# PERIPH.net
KiCad netlist of a schematic drawn in Altium Designer
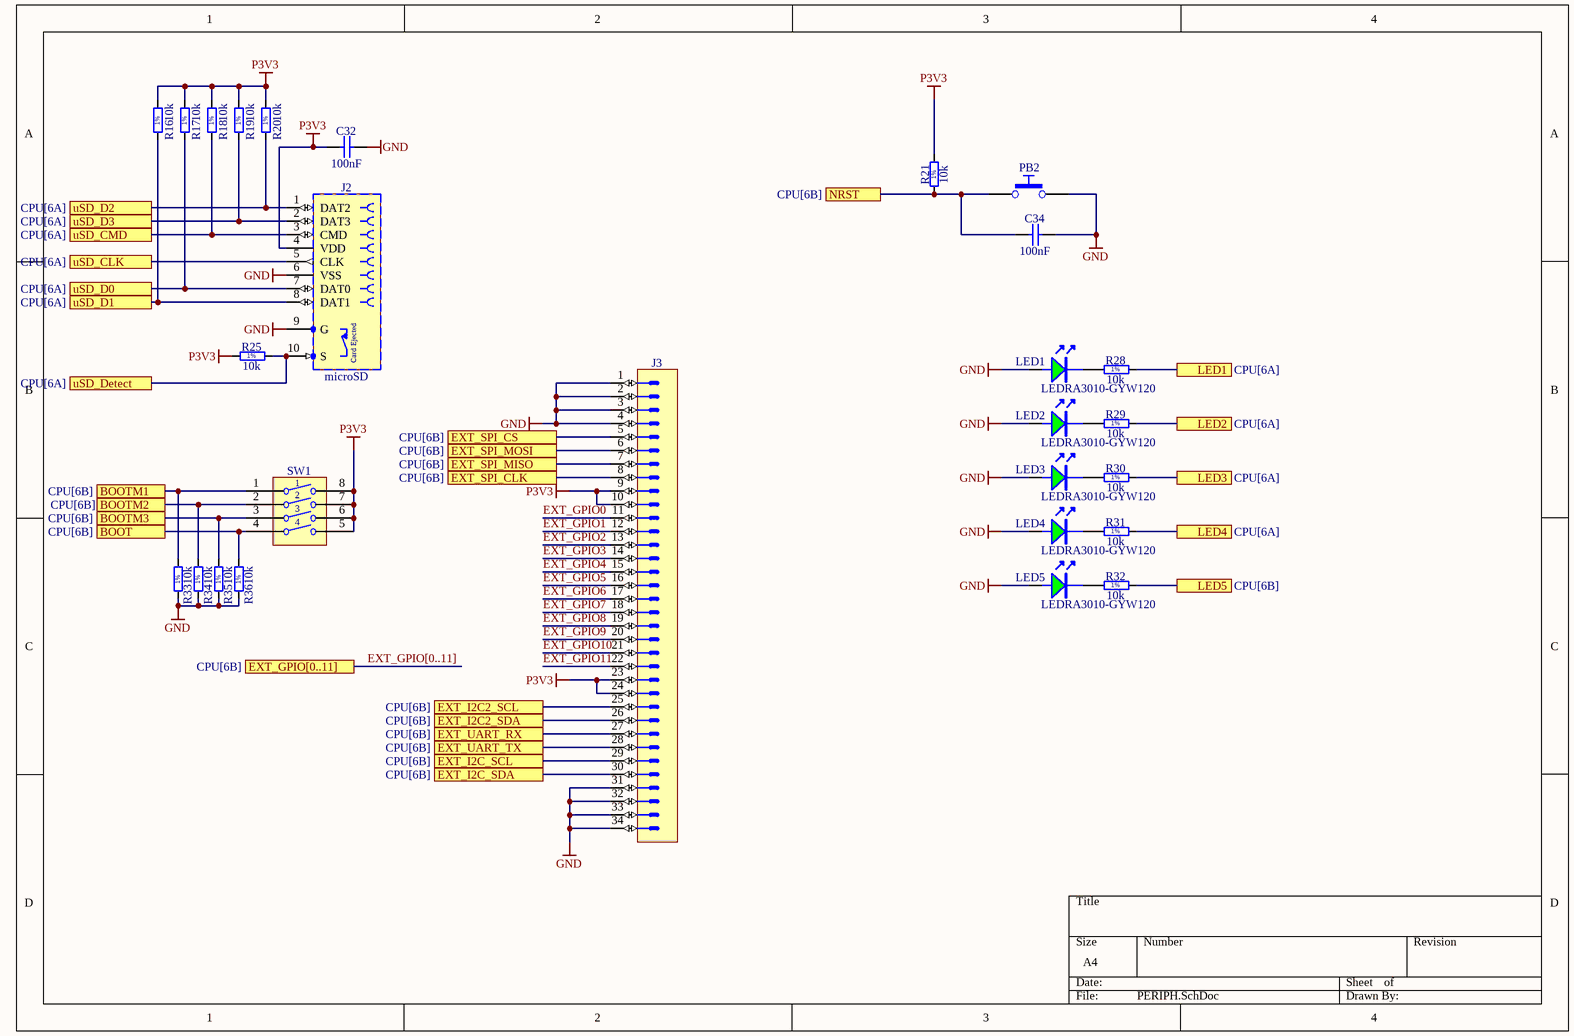
[diagram p0: PERIPH.SchDoc]

(export (version "E")
  (design (tool "Eeschema 10.0.6"))
  (components
    (comp (ref "C32")
      (value "100nF")
      (footprint "CAPC1005X55N")
      (description "Non-polarised capacitor")
      (fields
        (field (name "PART NUMBER") "CC0402_100NF_16V_10%_X5R")
        (field (name "VOLTAGE") "16V")
        (field (name "AUTHOR") "CERN DEM JLC")
      )
      (libsource (lib "Capacitors") (part "Capacitor - non polarized"))
    )
    (comp (ref "C34")
      (value "100nF")
      (footprint "CAPC1005X55N")
      (description "Non-polarised capacitor")
      (fields
        (field (name "PART NUMBER") "CC0402_100NF_16V_10%_X5R")
        (field (name "VOLTAGE") "16V")
        (field (name "AUTHOR") "CERN DEM JLC")
      )
      (libsource (lib "Capacitors") (part "Capacitor - non polarized"))
    )
    (comp (ref "J2")
      (value "microSD")
      (footprint "ATTEND_112A-TAAR-R03")
      (description "Connector MicroSD 8 Pin + Switch")
      (fields
        (field (name "PART NUMBER") "ATTEND_112A-TAAR-R03")
        (field (name "MANUFACTURER") "ATTEND")
        (field (name "AUTHOR") "CERN DEM JMW")
      )
      (libsource (lib "Connectors") (part "Connector MicroSD 8 Pin + Switch"))
    )
    (comp (ref "J3")
      (value "Header 34")
      (footprint "3M_N2534-6002RB")
      (description "Connector 34 Male")
      (fields
        (field (name "PART NUMBER") "3M_N2534-6002RB")
        (field (name "MANUFACTURER") "3M")
        (field (name "AUTHOR") "CERN DEM JLC")
      )
      (libsource (lib "Connectors") (part "Connector 34 Male"))
    )
    (comp (ref "LED1")
      (value "LEDRA3010-GYW120")
      (footprint "LED_KPA3010_G")
      (description "LED (Maritex)")
      (libsource (lib "Charger_base_station v2.2") (part "LED_SMD_90deg_G"))
    )
    (comp (ref "LED2")
      (value "LEDRA3010-GYW120")
      (footprint "LED_KPA3010_G")
      (description "LED (Maritex)")
      (libsource (lib "Charger_base_station v2.2") (part "LED_SMD_90deg_G"))
    )
    (comp (ref "LED3")
      (value "LEDRA3010-GYW120")
      (footprint "LED_KPA3010_G")
      (description "LED (Maritex)")
      (libsource (lib "Charger_base_station v2.2") (part "LED_SMD_90deg_G"))
    )
    (comp (ref "LED4")
      (value "LEDRA3010-GYW120")
      (footprint "LED_KPA3010_G")
      (description "LED (Maritex)")
      (libsource (lib "Charger_base_station v2.2") (part "LED_SMD_90deg_G"))
    )
    (comp (ref "LED5")
      (value "LEDRA3010-GYW120")
      (footprint "LED_KPA3010_G")
      (description "LED (Maritex)")
      (libsource (lib "Charger_base_station v2.2") (part "LED_SMD_90deg_G"))
    )
    (comp (ref "PB2")
      (value "Push Button")
      (footprint "PB_TYCO_FSMSM")
      (description "Push-Button Switch SPDT")
      (fields
        (field (name "PART NUMBER") "PB_TYCO_FSMSM")
        (field (name "MANUFACTURER") "TYCO ELECTRONICS")
        (field (name "AUTHOR") "CERN DEM JLC")
      )
      (libsource (lib "Eletro-mechanical") (part "PB SPST 1NO-2NO"))
    )
    (comp (ref "R16")
      (value "10k")
      (footprint "RESC1005X40N")
      (description "Resistor - 1%")
      (fields
        (field (name "PART NUMBER") "R0402_10K_1%_0.0625W_100PPM")
        (field (name "POWER") "0.0625W")
        (field (name "AUTHOR") "CERN DEM JLC")
      )
      (libsource (lib "Resistors") (part "Resistor - 1%"))
    )
    (comp (ref "R17")
      (value "10k")
      (footprint "RESC1005X40N")
      (description "Resistor - 1%")
      (fields
        (field (name "PART NUMBER") "R0402_10K_1%_0.0625W_100PPM")
        (field (name "POWER") "0.0625W")
        (field (name "AUTHOR") "CERN DEM JLC")
      )
      (libsource (lib "Resistors") (part "Resistor - 1%"))
    )
    (comp (ref "R18")
      (value "10k")
      (footprint "RESC1005X40N")
      (description "Resistor - 1%")
      (fields
        (field (name "PART NUMBER") "R0402_10K_1%_0.0625W_100PPM")
        (field (name "POWER") "0.0625W")
        (field (name "AUTHOR") "CERN DEM JLC")
      )
      (libsource (lib "Resistors") (part "Resistor - 1%"))
    )
    (comp (ref "R19")
      (value "10k")
      (footprint "RESC1005X40N")
      (description "Resistor - 1%")
      (fields
        (field (name "PART NUMBER") "R0402_10K_1%_0.0625W_100PPM")
        (field (name "POWER") "0.0625W")
        (field (name "AUTHOR") "CERN DEM JLC")
      )
      (libsource (lib "Resistors") (part "Resistor - 1%"))
    )
    (comp (ref "R20")
      (value "10k")
      (footprint "RESC1005X40N")
      (description "Resistor - 1%")
      (fields
        (field (name "PART NUMBER") "R0402_10K_1%_0.0625W_100PPM")
        (field (name "POWER") "0.0625W")
        (field (name "AUTHOR") "CERN DEM JLC")
      )
      (libsource (lib "Resistors") (part "Resistor - 1%"))
    )
    (comp (ref "R21")
      (value "10k")
      (footprint "RESC1005X40N")
      (description "Resistor - 1%")
      (fields
        (field (name "PART NUMBER") "R0402_10K_1%_0.0625W_100PPM")
        (field (name "POWER") "0.0625W")
        (field (name "AUTHOR") "CERN DEM JLC")
      )
      (libsource (lib "Resistors") (part "Resistor - 1%"))
    )
    (comp (ref "R25")
      (value "10k")
      (footprint "RESC1005X40N")
      (description "Resistor - 1%")
      (fields
        (field (name "PART NUMBER") "R0402_10K_1%_0.0625W_100PPM")
        (field (name "POWER") "0.0625W")
        (field (name "AUTHOR") "CERN DEM JLC")
      )
      (libsource (lib "Resistors") (part "Resistor - 1%"))
    )
    (comp (ref "R28")
      (value "10k")
      (footprint "RESC1005X40N")
      (description "Resistor - 1%")
      (fields
        (field (name "PART NUMBER") "R0402_10K_1%_0.0625W_100PPM")
        (field (name "POWER") "0.0625W")
        (field (name "AUTHOR") "CERN DEM JLC")
      )
      (libsource (lib "Resistors") (part "Resistor - 1%"))
    )
    (comp (ref "R29")
      (value "10k")
      (footprint "RESC1005X40N")
      (description "Resistor - 1%")
      (fields
        (field (name "PART NUMBER") "R0402_10K_1%_0.0625W_100PPM")
        (field (name "POWER") "0.0625W")
        (field (name "AUTHOR") "CERN DEM JLC")
      )
      (libsource (lib "Resistors") (part "Resistor - 1%"))
    )
    (comp (ref "R30")
      (value "10k")
      (footprint "RESC1005X40N")
      (description "Resistor - 1%")
      (fields
        (field (name "PART NUMBER") "R0402_10K_1%_0.0625W_100PPM")
        (field (name "POWER") "0.0625W")
        (field (name "AUTHOR") "CERN DEM JLC")
      )
      (libsource (lib "Resistors") (part "Resistor - 1%"))
    )
    (comp (ref "R31")
      (value "10k")
      (footprint "RESC1005X40N")
      (description "Resistor - 1%")
      (fields
        (field (name "PART NUMBER") "R0402_10K_1%_0.0625W_100PPM")
        (field (name "POWER") "0.0625W")
        (field (name "AUTHOR") "CERN DEM JLC")
      )
      (libsource (lib "Resistors") (part "Resistor - 1%"))
    )
    (comp (ref "R32")
      (value "10k")
      (footprint "RESC1005X40N")
      (description "Resistor - 1%")
      (fields
        (field (name "PART NUMBER") "R0402_10K_1%_0.0625W_100PPM")
        (field (name "POWER") "0.0625W")
        (field (name "AUTHOR") "CERN DEM JLC")
      )
      (libsource (lib "Resistors") (part "Resistor - 1%"))
    )
    (comp (ref "R33")
      (value "10k")
      (footprint "RESC1005X40N")
      (description "Resistor - 1%")
      (fields
        (field (name "PART NUMBER") "R0402_10K_1%_0.0625W_100PPM")
        (field (name "POWER") "0.0625W")
        (field (name "AUTHOR") "CERN DEM JLC")
      )
      (libsource (lib "Resistors") (part "Resistor - 1%"))
    )
    (comp (ref "R34")
      (value "10k")
      (footprint "RESC1005X40N")
      (description "Resistor - 1%")
      (fields
        (field (name "PART NUMBER") "R0402_10K_1%_0.0625W_100PPM")
        (field (name "POWER") "0.0625W")
        (field (name "AUTHOR") "CERN DEM JLC")
      )
      (libsource (lib "Resistors") (part "Resistor - 1%"))
    )
    (comp (ref "R35")
      (value "10k")
      (footprint "RESC1005X40N")
      (description "Resistor - 1%")
      (fields
        (field (name "PART NUMBER") "R0402_10K_1%_0.0625W_100PPM")
        (field (name "POWER") "0.0625W")
        (field (name "AUTHOR") "CERN DEM JLC")
      )
      (libsource (lib "Resistors") (part "Resistor - 1%"))
    )
    (comp (ref "R36")
      (value "10k")
      (footprint "RESC1005X40N")
      (description "Resistor - 1%")
      (fields
        (field (name "PART NUMBER") "R0402_10K_1%_0.0625W_100PPM")
        (field (name "POWER") "0.0625W")
        (field (name "AUTHOR") "CERN DEM JLC")
      )
      (libsource (lib "Resistors") (part "Resistor - 1%"))
    )
    (comp (ref "SW1")
      (value "Switch")
      (footprint "SW_CTS_219-4MST")
      (description "4 Ways SPST DIP Switch")
      (fields
        (field (name "PART NUMBER") "SW_CTS_219-4MST")
        (field (name "MANUFACTURER") "CTS ELECTROCOMPONENTS")
        (field (name "AUTHOR") "CERN DEM JLC")
      )
      (libsource (lib "Eletro-mechanical") (part "SW 4x SPST DIP Switch"))
    )
  )
  (nets
    (net (code "1") (name "/BOOT") (class "Default")
      (node (ref "R36") (pin "2") (pinfunction "2_2") (pintype "passive"))
      (node (ref "SW1") (pin "4") (pinfunction "4_4") (pintype "passive"))
    )
    (net (code "2") (name "/BOOTM1") (class "Default")
      (node (ref "R33") (pin "2") (pinfunction "2_2") (pintype "passive"))
      (node (ref "SW1") (pin "1") (pinfunction "1_1") (pintype "passive"))
    )
    (net (code "3") (name "/BOOTM2") (class "Default")
      (node (ref "R34") (pin "2") (pinfunction "2_2") (pintype "passive"))
      (node (ref "SW1") (pin "2") (pinfunction "2_2") (pintype "passive"))
    )
    (net (code "4") (name "/BOOTM3") (class "Default")
      (node (ref "R35") (pin "2") (pinfunction "2_2") (pintype "passive"))
      (node (ref "SW1") (pin "3") (pinfunction "3_3") (pintype "passive"))
    )
    (net (code "5") (name "/EXT_GPIO0") (class "Default")
      (node (ref "J3") (pin "11") (pinfunction "11_11") (pintype "bidirectional"))
    )
    (net (code "6") (name "/EXT_GPIO1") (class "Default")
      (node (ref "J3") (pin "12") (pinfunction "12_12") (pintype "bidirectional"))
    )
    (net (code "7") (name "/EXT_GPIO2") (class "Default")
      (node (ref "J3") (pin "13") (pinfunction "13_13") (pintype "bidirectional"))
    )
    (net (code "8") (name "/EXT_GPIO3") (class "Default")
      (node (ref "J3") (pin "14") (pinfunction "14_14") (pintype "bidirectional"))
    )
    (net (code "9") (name "/EXT_GPIO4") (class "Default")
      (node (ref "J3") (pin "15") (pinfunction "15_15") (pintype "bidirectional"))
    )
    (net (code "10") (name "/EXT_GPIO5") (class "Default")
      (node (ref "J3") (pin "16") (pinfunction "16_16") (pintype "bidirectional"))
    )
    (net (code "11") (name "/EXT_GPIO6") (class "Default")
      (node (ref "J3") (pin "17") (pinfunction "17_17") (pintype "bidirectional"))
    )
    (net (code "12") (name "/EXT_GPIO7") (class "Default")
      (node (ref "J3") (pin "18") (pinfunction "18_18") (pintype "bidirectional"))
    )
    (net (code "13") (name "/EXT_GPIO8") (class "Default")
      (node (ref "J3") (pin "19") (pinfunction "19_19") (pintype "bidirectional"))
    )
    (net (code "14") (name "/EXT_GPIO9") (class "Default")
      (node (ref "J3") (pin "20") (pinfunction "20_20") (pintype "bidirectional"))
    )
    (net (code "15") (name "/EXT_GPIO10") (class "Default")
      (node (ref "J3") (pin "21") (pinfunction "21_21") (pintype "bidirectional"))
    )
    (net (code "16") (name "/EXT_GPIO11") (class "Default")
      (node (ref "J3") (pin "22") (pinfunction "22_22") (pintype "bidirectional"))
    )
    (net (code "18") (name "/EXT_I2C2_SCL") (class "Default")
      (node (ref "J3") (pin "25") (pinfunction "25_25") (pintype "bidirectional"))
    )
    (net (code "19") (name "/EXT_I2C2_SDA") (class "Default")
      (node (ref "J3") (pin "26") (pinfunction "26_26") (pintype "bidirectional"))
    )
    (net (code "20") (name "/EXT_I2C_SCL") (class "Default")
      (node (ref "J3") (pin "29") (pinfunction "29_29") (pintype "bidirectional"))
    )
    (net (code "21") (name "/EXT_I2C_SDA") (class "Default")
      (node (ref "J3") (pin "30") (pinfunction "30_30") (pintype "bidirectional"))
    )
    (net (code "22") (name "/EXT_SPI_CLK") (class "Default")
      (node (ref "J3") (pin "8") (pinfunction "8_8") (pintype "bidirectional"))
    )
    (net (code "23") (name "/EXT_SPI_CS") (class "Default")
      (node (ref "J3") (pin "5") (pinfunction "5_5") (pintype "bidirectional"))
    )
    (net (code "24") (name "/EXT_SPI_MISO") (class "Default")
      (node (ref "J3") (pin "7") (pinfunction "7_7") (pintype "bidirectional"))
    )
    (net (code "25") (name "/EXT_SPI_MOSI") (class "Default")
      (node (ref "J3") (pin "6") (pinfunction "6_6") (pintype "bidirectional"))
    )
    (net (code "26") (name "/EXT_UART_RX") (class "Default")
      (node (ref "J3") (pin "27") (pinfunction "27_27") (pintype "bidirectional"))
    )
    (net (code "27") (name "/EXT_UART_TX") (class "Default")
      (node (ref "J3") (pin "28") (pinfunction "28_28") (pintype "bidirectional"))
    )
    (net (code "28") (name "/LED1") (class "Default")
      (node (ref "R28") (pin "2") (pinfunction "2_2") (pintype "passive"))
    )
    (net (code "29") (name "/LED2") (class "Default")
      (node (ref "R29") (pin "2") (pinfunction "2_2") (pintype "passive"))
    )
    (net (code "30") (name "/LED3") (class "Default")
      (node (ref "R30") (pin "2") (pinfunction "2_2") (pintype "passive"))
    )
    (net (code "31") (name "/LED4") (class "Default")
      (node (ref "R31") (pin "2") (pinfunction "2_2") (pintype "passive"))
    )
    (net (code "32") (name "/LED5") (class "Default")
      (node (ref "R32") (pin "2") (pinfunction "2_2") (pintype "passive"))
    )
    (net (code "33") (name "/NRST") (class "Default")
      (node (ref "C34") (pin "1") (pinfunction "1_1") (pintype "passive"))
      (node (ref "PB2") (pin "1") (pinfunction "1_1") (pintype "passive"))
      (node (ref "R21") (pin "1") (pinfunction "1_1") (pintype "passive"))
    )
    (net (code "34") (name "/uSD_CLK") (class "Default")
      (node (ref "J2") (pin "5") (pinfunction "CLK_5") (pintype "output"))
    )
    (net (code "35") (name "/uSD_CMD") (class "Default")
      (node (ref "J2") (pin "3") (pinfunction "CMD_3") (pintype "bidirectional"))
      (node (ref "R18") (pin "1") (pinfunction "1_1") (pintype "passive"))
    )
    (net (code "36") (name "/uSD_D0") (class "Default")
      (node (ref "J2") (pin "7") (pinfunction "DAT0_7") (pintype "bidirectional"))
      (node (ref "R17") (pin "1") (pinfunction "1_1") (pintype "passive"))
    )
    (net (code "37") (name "/uSD_D1") (class "Default")
      (node (ref "J2") (pin "8") (pinfunction "DAT1_8") (pintype "bidirectional"))
      (node (ref "R16") (pin "1") (pinfunction "1_1") (pintype "passive"))
    )
    (net (code "38") (name "/uSD_D2") (class "Default")
      (node (ref "J2") (pin "1") (pinfunction "DAT2_1") (pintype "bidirectional"))
      (node (ref "R20") (pin "1") (pinfunction "1_1") (pintype "passive"))
    )
    (net (code "39") (name "/uSD_D3") (class "Default")
      (node (ref "J2") (pin "2") (pinfunction "DAT3_2") (pintype "bidirectional"))
      (node (ref "R19") (pin "1") (pinfunction "1_1") (pintype "passive"))
    )
    (net (code "40") (name "/uSD_Detect") (class "Default")
      (node (ref "J2") (pin "10") (pinfunction "S_10") (pintype "input"))
      (node (ref "R25") (pin "1") (pinfunction "1_1") (pintype "passive"))
    )
    (net (code "41") (name "GND") (class "Default")
      (node (ref "C32") (pin "2") (pinfunction "2_2") (pintype "passive"))
      (node (ref "C34") (pin "2") (pinfunction "2_2") (pintype "passive"))
      (node (ref "J2") (pin "6") (pinfunction "VSS_6") (pintype "power_in"))
      (node (ref "J2") (pin "9") (pinfunction "G_9") (pintype "power_in"))
      (node (ref "J3") (pin "1") (pinfunction "1_1") (pintype "bidirectional"))
      (node (ref "J3") (pin "2") (pinfunction "2_2") (pintype "bidirectional"))
      (node (ref "J3") (pin "3") (pinfunction "3_3") (pintype "bidirectional"))
      (node (ref "J3") (pin "31") (pinfunction "31_31") (pintype "bidirectional"))
      (node (ref "J3") (pin "32") (pinfunction "32_32") (pintype "bidirectional"))
      (node (ref "J3") (pin "33") (pinfunction "33_33") (pintype "bidirectional"))
      (node (ref "J3") (pin "34") (pinfunction "34_34") (pintype "bidirectional"))
      (node (ref "J3") (pin "4") (pinfunction "4_4") (pintype "bidirectional"))
      (node (ref "LED1") (pin "A") (pinfunction "A_A") (pintype "passive"))
      (node (ref "LED2") (pin "A") (pinfunction "A_A") (pintype "passive"))
      (node (ref "LED3") (pin "A") (pinfunction "A_A") (pintype "passive"))
      (node (ref "LED4") (pin "A") (pinfunction "A_A") (pintype "passive"))
      (node (ref "LED5") (pin "A") (pinfunction "A_A") (pintype "passive"))
      (node (ref "PB2") (pin "2") (pinfunction "2_2") (pintype "passive"))
      (node (ref "R33") (pin "1") (pinfunction "1_1") (pintype "passive"))
      (node (ref "R34") (pin "1") (pinfunction "1_1") (pintype "passive"))
      (node (ref "R35") (pin "1") (pinfunction "1_1") (pintype "passive"))
      (node (ref "R36") (pin "1") (pinfunction "1_1") (pintype "passive"))
    )
    (net (code "42") (name "Net-(LED1-PadK)") (class "Default")
      (node (ref "LED1") (pin "K") (pinfunction "K_K") (pintype "passive"))
      (node (ref "R28") (pin "1") (pinfunction "1_1") (pintype "passive"))
    )
    (net (code "43") (name "Net-(LED2-PadK)") (class "Default")
      (node (ref "LED2") (pin "K") (pinfunction "K_K") (pintype "passive"))
      (node (ref "R29") (pin "1") (pinfunction "1_1") (pintype "passive"))
    )
    (net (code "44") (name "Net-(LED3-PadK)") (class "Default")
      (node (ref "LED3") (pin "K") (pinfunction "K_K") (pintype "passive"))
      (node (ref "R30") (pin "1") (pinfunction "1_1") (pintype "passive"))
    )
    (net (code "45") (name "Net-(LED4-PadK)") (class "Default")
      (node (ref "LED4") (pin "K") (pinfunction "K_K") (pintype "passive"))
      (node (ref "R31") (pin "1") (pinfunction "1_1") (pintype "passive"))
    )
    (net (code "46") (name "Net-(LED5-PadK)") (class "Default")
      (node (ref "LED5") (pin "K") (pinfunction "K_K") (pintype "passive"))
      (node (ref "R32") (pin "1") (pinfunction "1_1") (pintype "passive"))
    )
    (net (code "47") (name "P3V3") (class "Default")
      (node (ref "C32") (pin "1") (pinfunction "1_1") (pintype "passive"))
      (node (ref "J2") (pin "4") (pinfunction "VDD_4") (pintype "power_in"))
      (node (ref "J3") (pin "10") (pinfunction "10_10") (pintype "bidirectional"))
      (node (ref "J3") (pin "23") (pinfunction "23_23") (pintype "bidirectional"))
      (node (ref "J3") (pin "24") (pinfunction "24_24") (pintype "bidirectional"))
      (node (ref "J3") (pin "9") (pinfunction "9_9") (pintype "bidirectional"))
      (node (ref "R16") (pin "2") (pinfunction "2_2") (pintype "passive"))
      (node (ref "R17") (pin "2") (pinfunction "2_2") (pintype "passive"))
      (node (ref "R18") (pin "2") (pinfunction "2_2") (pintype "passive"))
      (node (ref "R19") (pin "2") (pinfunction "2_2") (pintype "passive"))
      (node (ref "R20") (pin "2") (pinfunction "2_2") (pintype "passive"))
      (node (ref "R21") (pin "2") (pinfunction "2_2") (pintype "passive"))
      (node (ref "R25") (pin "2") (pinfunction "2_2") (pintype "passive"))
      (node (ref "SW1") (pin "5") (pinfunction "5_5") (pintype "passive"))
      (node (ref "SW1") (pin "6") (pinfunction "6_6") (pintype "passive"))
      (node (ref "SW1") (pin "7") (pinfunction "7_7") (pintype "passive"))
      (node (ref "SW1") (pin "8") (pinfunction "8_8") (pintype "passive"))
    )
  )
)
